# MCU.net
KiCad netlist of a schematic drawn in Altium Designer
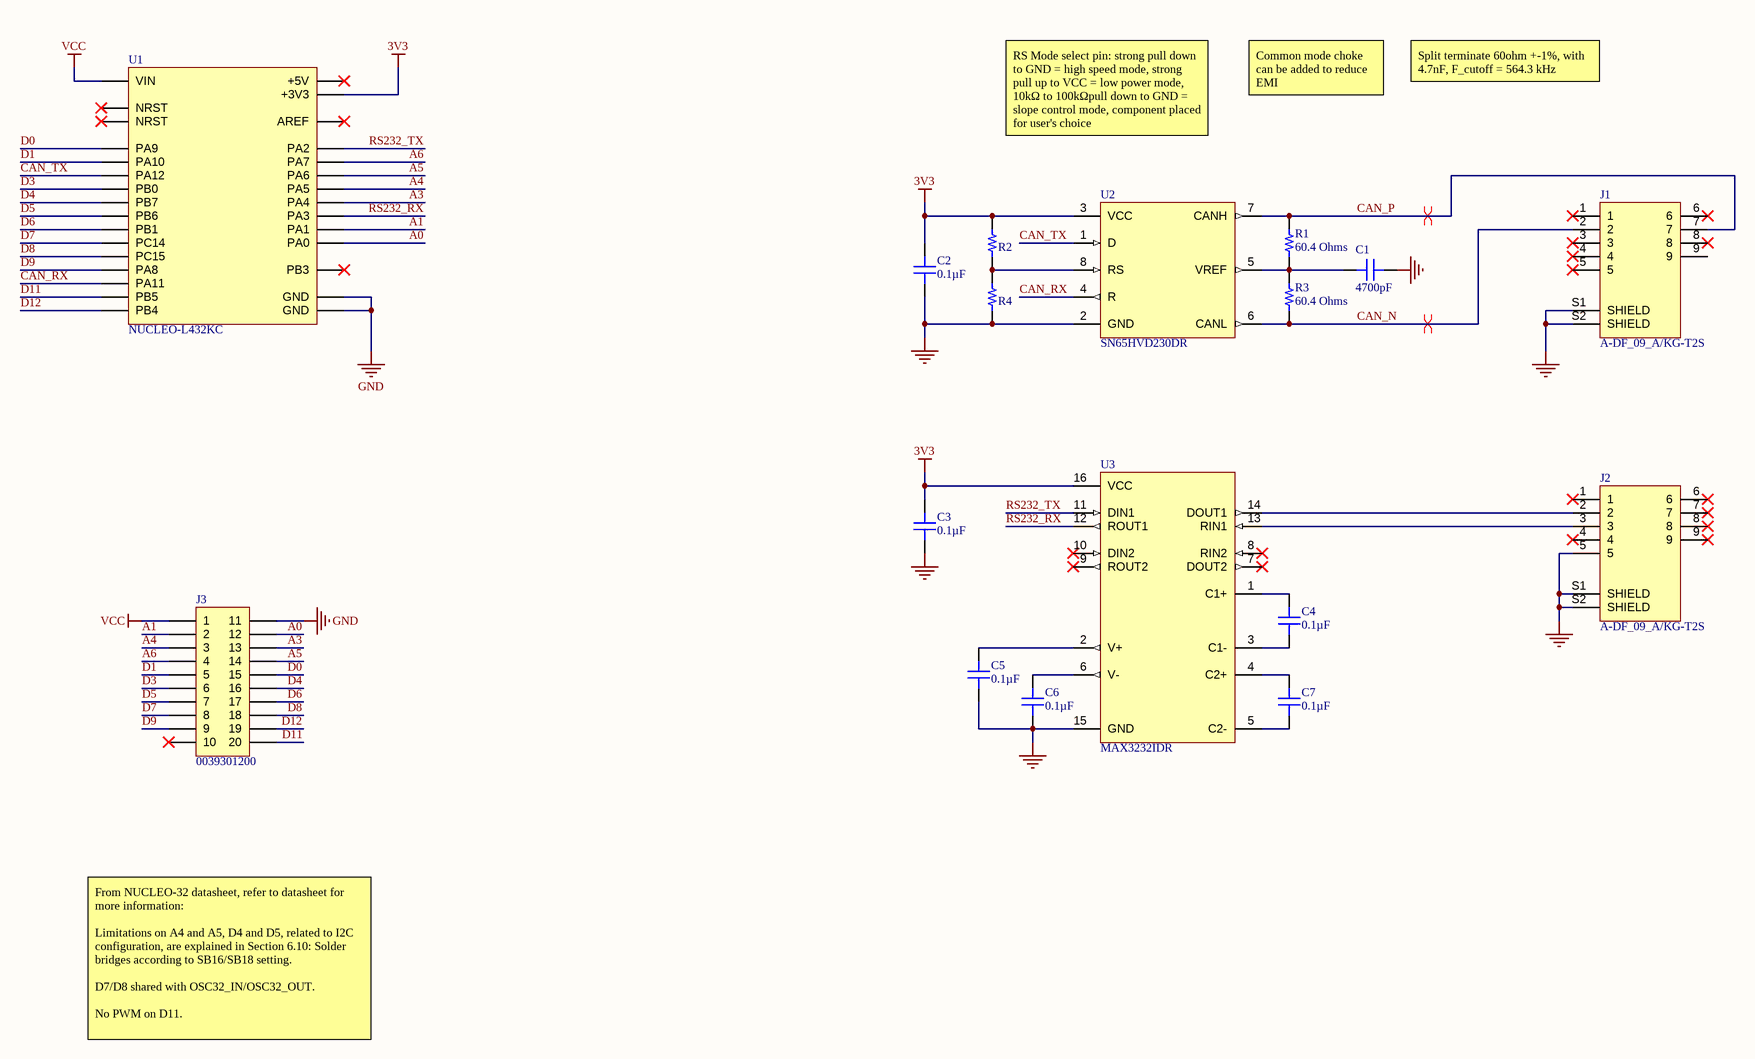
[diagram p0: MCU.SchDoc]

(export (version "E")
  (design (tool "Eeschema 10.0.6"))
  (components
    (comp (ref "C1")
      (value "4700pF")
      (footprint "CAP 0603_1608")
      (description "CAP CER 4700PF 50V X7R 0603")
      (fields
        (field (name "PART NUMBER") "CGA3E2X7R1H472K080AA")
        (field (name "MANUFACTURER") "TDK Corporation")
      )
      (libsource (lib "Celestial Altium Library - altium_library") (part "Capacitor"))
    )
    (comp (ref "C2")
      (value "0.1µF")
      (footprint "CAP 0603_1608")
      (description "CAP CER 0.1UF 25V X7R 0603")
      (fields
        (field (name "PART NUMBER") "CL10B104KA8NNNC")
        (field (name "MANUFACTURER") "Samsung Electro-Mechanics")
      )
      (libsource (lib "Celestial Altium Library - altium_library") (part "Capacitor"))
    )
    (comp (ref "C3")
      (value "0.1µF")
      (footprint "CAP 0603_1608")
      (description "CAP CER 0.1UF 25V X7R 0603")
      (fields
        (field (name "PART NUMBER") "CL10B104KA8NNNC")
        (field (name "MANUFACTURER") "Samsung Electro-Mechanics")
      )
      (libsource (lib "Celestial Altium Library - altium_library") (part "Capacitor"))
    )
    (comp (ref "C4")
      (value "0.1µF")
      (footprint "CAP 0603_1608")
      (description "CAP CER 0.1UF 25V X7R 0603")
      (fields
        (field (name "PART NUMBER") "CL10B104KA8NNNC")
        (field (name "MANUFACTURER") "Samsung Electro-Mechanics")
      )
      (libsource (lib "Celestial Altium Library - altium_library") (part "Capacitor"))
    )
    (comp (ref "C5")
      (value "0.1µF")
      (footprint "CAP 0603_1608")
      (description "CAP CER 0.1UF 25V X7R 0603")
      (fields
        (field (name "PART NUMBER") "CL10B104KA8NNNC")
        (field (name "MANUFACTURER") "Samsung Electro-Mechanics")
      )
      (libsource (lib "Celestial Altium Library - altium_library") (part "Capacitor"))
    )
    (comp (ref "C6")
      (value "0.1µF")
      (footprint "CAP 0603_1608")
      (description "CAP CER 0.1UF 25V X7R 0603")
      (fields
        (field (name "PART NUMBER") "CL10B104KA8NNNC")
        (field (name "MANUFACTURER") "Samsung Electro-Mechanics")
      )
      (libsource (lib "Celestial Altium Library - altium_library") (part "Capacitor"))
    )
    (comp (ref "C7")
      (value "0.1µF")
      (footprint "CAP 0603_1608")
      (description "CAP CER 0.1UF 25V X7R 0603")
      (fields
        (field (name "PART NUMBER") "CL10B104KA8NNNC")
        (field (name "MANUFACTURER") "Samsung Electro-Mechanics")
      )
      (libsource (lib "Celestial Altium Library - altium_library") (part "Capacitor"))
    )
    (comp (ref "J1")
      (value "A-DF_09_A/KG-T2S")
      (footprint "ASSMANN_A-DF09A/KG-T2S")
      (description "Conn D-Subminiature F 9 POS 2.77mm Solder RA Thru-Hole 9 Terminal 1 Port")
      (fields (field (name "MF") "{'manufacturer': u'Assmann WSW'}"))
      (libsource (lib "RTC_Mini_Symbols") (part "A-DF_09_A/KG-T2S"))
    )
    (comp (ref "J2")
      (value "A-DF_09_A/KG-T2S")
      (footprint "ASSMANN_A-DF09A/KG-T2S")
      (description "Conn D-Subminiature F 9 POS 2.77mm Solder RA Thru-Hole 9 Terminal 1 Port")
      (fields (field (name "MF") "{'manufacturer': u'Assmann WSW'}"))
      (libsource (lib "RTC_Mini_Symbols") (part "A-DF_09_A/KG-T2S"))
    )
    (comp (ref "J3")
      (value "0039301200")
      (footprint "MOLEX_0039301200")
      (description "Connector Header Through Hole, Right Angle 20 position 0.165\" (4.20mm)")
      (libsource (lib "RTC_Mini_Symbols") (part "0039301200"))
    )
    (comp (ref "R1")
      (value "60.4 Ohms")
      (footprint "RES 0603_1608")
      (description "RES 60.4 OHM 1% 1/10W 0603")
      (fields
        (field (name "PART NUMBER") "RMCF0603FT60R4")
        (field (name "MANUFACTURER") "Stackpole Electronics Inc")
      )
      (libsource (lib "Celestial Altium Library - altium_library") (part "Resistor"))
    )
    (comp (ref "R2")
      (value "~")
      (footprint "RES 0805_2012")
      (description "RES SMD 0 OHM JUMP 1/8W 0805")
      (fields (field (name "PART NUMBER") "CRCW08050000Z0EAC") (field (name "MANUFACTURER") "Vishay Dale"))
      (libsource (lib "Celestial Altium Library - altium_library") (part "Resistor"))
    )
    (comp (ref "R3")
      (value "60.4 Ohms")
      (footprint "RES 0603_1608")
      (description "RES 60.4 OHM 1% 1/10W 0603")
      (fields
        (field (name "PART NUMBER") "RMCF0603FT60R4")
        (field (name "MANUFACTURER") "Stackpole Electronics Inc")
      )
      (libsource (lib "Celestial Altium Library - altium_library") (part "Resistor"))
    )
    (comp (ref "R4")
      (value "~")
      (footprint "RES 0805_2012")
      (description "RES SMD 0 OHM JUMP 1/8W 0805")
      (fields (field (name "PART NUMBER") "CRCW08050000Z0EAC") (field (name "MANUFACTURER") "Vishay Dale"))
      (libsource (lib "Celestial Altium Library - altium_library") (part "Resistor"))
    )
    (comp (ref "U1")
      (value "NUCLEO-L432KC")
      (footprint "MODULE_NUCLEO-L432KC")
      (description "STM32 Nucleo-32 development board with STM32L432KC MCU, supports Arduino connectivity")
      (fields (field (name "MF") "{'manufacturer': u'STMicroelectronics'}"))
      (libsource (lib "RTC_Mini_Symbols") (part "NUCLEO-L432KC"))
    )
    (comp (ref "U2")
      (value "SN65HVD230DR")
      (footprint "SOIC127P599X175-8N")
      (description "3.3 V CAN Transceiver with Standby Mode 8-SOIC -40 to 85")
      (fields (field (name "MF") "{'manufacturer': u'Texas Instruments'}"))
      (libsource (lib "RTC_Mini_Symbols") (part "SN65HVD230DR"))
    )
    (comp (ref "U3")
      (value "MAX3232IDR")
      (footprint "SOIC127P600X175-16N")
      (description "3-V to 5.5-V multichannel RS-232 line driver & receiver 16-SOIC -40 to 85")
      (fields (field (name "MF") "{'manufacturer': u'Texas Instruments'}"))
      (libsource (lib "RTC_Mini_Symbols") (part "MAX3232IDR"))
    )
  )
  (nets
    (net (code "1") (name "/A0") (class "Default")
      (node (ref "J3") (pin "12") (pinfunction "12_12") (pintype "passive"))
      (node (ref "U1") (pin "CN4_12") (pinfunction "PA0_CN4_12") (pintype "passive"))
    )
    (net (code "2") (name "/A1") (class "Default")
      (node (ref "J3") (pin "2") (pinfunction "2_2") (pintype "passive"))
      (node (ref "U1") (pin "CN4_11") (pinfunction "PA1_CN4_11") (pintype "passive"))
    )
    (net (code "3") (name "/A3") (class "Default")
      (node (ref "J3") (pin "13") (pinfunction "13_13") (pintype "passive"))
      (node (ref "U1") (pin "CN4_9") (pinfunction "PA4_CN4_9") (pintype "passive"))
    )
    (net (code "4") (name "/A4") (class "Default")
      (node (ref "J3") (pin "3") (pinfunction "3_3") (pintype "passive"))
      (node (ref "U1") (pin "CN4_8") (pinfunction "PA5_CN4_8") (pintype "passive"))
    )
    (net (code "5") (name "/A5") (class "Default")
      (node (ref "J3") (pin "14") (pinfunction "14_14") (pintype "passive"))
      (node (ref "U1") (pin "CN4_7") (pinfunction "PA6_CN4_7") (pintype "passive"))
    )
    (net (code "6") (name "/A6") (class "Default")
      (node (ref "J3") (pin "4") (pinfunction "4_4") (pintype "passive"))
      (node (ref "U1") (pin "CN4_6") (pinfunction "PA7_CN4_6") (pintype "passive"))
    )
    (net (code "7") (name "/CAN_N") (class "Default")
      (node (ref "J1") (pin "2") (pinfunction "2_2") (pintype "passive"))
      (node (ref "R3") (pin "2") (pinfunction "2_2") (pintype "passive"))
      (node (ref "U2") (pin "6") (pinfunction "CANL_6") (pintype "output"))
    )
    (net (code "8") (name "/CAN_P") (class "Default")
      (node (ref "J1") (pin "7") (pinfunction "7_7") (pintype "passive"))
      (node (ref "R1") (pin "1") (pinfunction "1_1") (pintype "passive"))
      (node (ref "U2") (pin "7") (pinfunction "CANH_7") (pintype "output"))
    )
    (net (code "9") (name "/CAN_RX") (class "Default")
      (node (ref "U1") (pin "CN3_13") (pinfunction "PA11_CN3_13") (pintype "passive"))
      (node (ref "U2") (pin "4") (pinfunction "R_4") (pintype "output"))
    )
    (net (code "10") (name "/CAN_TX") (class "Default")
      (node (ref "U1") (pin "CN3_5") (pinfunction "PA12_CN3_5") (pintype "passive"))
      (node (ref "U2") (pin "1") (pinfunction "D_1") (pintype "input"))
    )
    (net (code "11") (name "/D0") (class "Default")
      (node (ref "J3") (pin "15") (pinfunction "15_15") (pintype "passive"))
      (node (ref "U1") (pin "CN3_1") (pinfunction "PA9_CN3_1") (pintype "passive"))
    )
    (net (code "12") (name "/D1") (class "Default")
      (node (ref "J3") (pin "5") (pinfunction "5_5") (pintype "passive"))
      (node (ref "U1") (pin "CN3_2") (pinfunction "PA10_CN3_2") (pintype "passive"))
    )
    (net (code "13") (name "/D3") (class "Default")
      (node (ref "J3") (pin "6") (pinfunction "6_6") (pintype "passive"))
      (node (ref "U1") (pin "CN3_6") (pinfunction "PB0_CN3_6") (pintype "passive"))
    )
    (net (code "14") (name "/D4") (class "Default")
      (node (ref "J3") (pin "16") (pinfunction "16_16") (pintype "passive"))
      (node (ref "U1") (pin "CN3_7") (pinfunction "PB7_CN3_7") (pintype "passive"))
    )
    (net (code "15") (name "/D5") (class "Default")
      (node (ref "J3") (pin "7") (pinfunction "7_7") (pintype "passive"))
      (node (ref "U1") (pin "CN3_8") (pinfunction "PB6_CN3_8") (pintype "passive"))
    )
    (net (code "16") (name "/D6") (class "Default")
      (node (ref "J3") (pin "17") (pinfunction "17_17") (pintype "passive"))
      (node (ref "U1") (pin "CN3_9") (pinfunction "PB1_CN3_9") (pintype "passive"))
    )
    (net (code "17") (name "/D7") (class "Default")
      (node (ref "J3") (pin "8") (pinfunction "8_8") (pintype "passive"))
      (node (ref "U1") (pin "CN3_10") (pinfunction "PC14_CN3_10") (pintype "passive"))
    )
    (net (code "18") (name "/D8") (class "Default")
      (node (ref "J3") (pin "18") (pinfunction "18_18") (pintype "passive"))
      (node (ref "U1") (pin "CN3_11") (pinfunction "PC15_CN3_11") (pintype "passive"))
    )
    (net (code "19") (name "/D9") (class "Default")
      (node (ref "J3") (pin "9") (pinfunction "9_9") (pintype "passive"))
      (node (ref "U1") (pin "CN3_12") (pinfunction "PA8_CN3_12") (pintype "passive"))
    )
    (net (code "20") (name "/D11") (class "Default")
      (node (ref "J3") (pin "20") (pinfunction "20_20") (pintype "passive"))
      (node (ref "U1") (pin "CN3_14") (pinfunction "PB5_CN3_14") (pintype "passive"))
    )
    (net (code "21") (name "/D12") (class "Default")
      (node (ref "J3") (pin "19") (pinfunction "19_19") (pintype "passive"))
      (node (ref "U1") (pin "CN3_15") (pinfunction "PB4_CN3_15") (pintype "passive"))
    )
    (net (code "22") (name "/RS232_RX") (class "Default")
      (node (ref "U1") (pin "CN4_10") (pinfunction "PA3_CN4_10") (pintype "passive"))
      (node (ref "U3") (pin "12") (pinfunction "ROUT1_12") (pintype "output"))
    )
    (net (code "23") (name "/RS232_TX") (class "Default")
      (node (ref "U1") (pin "CN4_5") (pinfunction "PA2_CN4_5") (pintype "passive"))
      (node (ref "U3") (pin "11") (pinfunction "DIN1_11") (pintype "input"))
    )
    (net (code "24") (name "3V3") (class "Default")
      (node (ref "C2") (pin "2") (pinfunction "2_2") (pintype "passive"))
      (node (ref "C3") (pin "2") (pinfunction "2_2") (pintype "passive"))
      (node (ref "R2") (pin "2") (pinfunction "2_2") (pintype "passive"))
      (node (ref "U1") (pin "CN4_14") (pinfunction "+3V3_CN4_14") (pintype "power_in"))
      (node (ref "U2") (pin "3") (pinfunction "VCC_3") (pintype "power_in"))
      (node (ref "U3") (pin "16") (pinfunction "VCC_16") (pintype "power_in"))
    )
    (net (code "25") (name "GND") (class "Default")
      (node (ref "C1") (pin "2") (pinfunction "2_2") (pintype "passive"))
      (node (ref "C2") (pin "1") (pinfunction "1_1") (pintype "passive"))
      (node (ref "C3") (pin "1") (pinfunction "1_1") (pintype "passive"))
      (node (ref "C5") (pin "1") (pinfunction "1_1") (pintype "passive"))
      (node (ref "C6") (pin "1") (pinfunction "1_1") (pintype "passive"))
      (node (ref "J1") (pin "S1") (pinfunction "SHIELD_S1") (pintype "passive"))
      (node (ref "J1") (pin "S2") (pinfunction "SHIELD_S2") (pintype "passive"))
      (node (ref "J2") (pin "5") (pinfunction "5_5") (pintype "passive"))
      (node (ref "J2") (pin "S1") (pinfunction "SHIELD_S1") (pintype "passive"))
      (node (ref "J2") (pin "S2") (pinfunction "SHIELD_S2") (pintype "passive"))
      (node (ref "J3") (pin "11") (pinfunction "11_11") (pintype "passive"))
      (node (ref "R4") (pin "1") (pinfunction "1_1") (pintype "passive"))
      (node (ref "U1") (pin "CN3_4") (pinfunction "GND_CN3_4") (pintype "power_in"))
      (node (ref "U1") (pin "CN4_2") (pinfunction "GND_CN4_2") (pintype "power_in"))
      (node (ref "U2") (pin "2") (pinfunction "GND_2") (pintype "power_in"))
      (node (ref "U3") (pin "15") (pinfunction "GND_15") (pintype "power_in"))
    )
    (net (code "26") (name "Net-(U2-RS)") (class "Default")
      (node (ref "R2") (pin "1") (pinfunction "1_1") (pintype "passive"))
      (node (ref "R4") (pin "2") (pinfunction "2_2") (pintype "passive"))
      (node (ref "U2") (pin "8") (pinfunction "RS_8") (pintype "input"))
    )
    (net (code "27") (name "Net-(U2-VREF)") (class "Default")
      (node (ref "C1") (pin "1") (pinfunction "1_1") (pintype "passive"))
      (node (ref "R1") (pin "2") (pinfunction "2_2") (pintype "passive"))
      (node (ref "R3") (pin "1") (pinfunction "1_1") (pintype "passive"))
      (node (ref "U2") (pin "5") (pinfunction "VREF_5") (pintype "output"))
    )
    (net (code "28") (name "Net-(U3-C1+)") (class "Default")
      (node (ref "C4") (pin "2") (pinfunction "2_2") (pintype "passive"))
      (node (ref "U3") (pin "1") (pinfunction "C1+_1") (pintype "passive"))
    )
    (net (code "29") (name "Net-(U3-C1-)") (class "Default")
      (node (ref "C4") (pin "1") (pinfunction "1_1") (pintype "passive"))
      (node (ref "U3") (pin "3") (pinfunction "C1-_3") (pintype "passive"))
    )
    (net (code "30") (name "Net-(U3-C2+)") (class "Default")
      (node (ref "C7") (pin "2") (pinfunction "2_2") (pintype "passive"))
      (node (ref "U3") (pin "4") (pinfunction "C2+_4") (pintype "passive"))
    )
    (net (code "31") (name "Net-(U3-C2-)") (class "Default")
      (node (ref "C7") (pin "1") (pinfunction "1_1") (pintype "passive"))
      (node (ref "U3") (pin "5") (pinfunction "C2-_5") (pintype "passive"))
    )
    (net (code "32") (name "Net-(U3-DOUT1)") (class "Default")
      (node (ref "J2") (pin "2") (pinfunction "2_2") (pintype "passive"))
      (node (ref "U3") (pin "14") (pinfunction "DOUT1_14") (pintype "output"))
    )
    (net (code "33") (name "Net-(U3-RIN1)") (class "Default")
      (node (ref "J2") (pin "3") (pinfunction "3_3") (pintype "passive"))
      (node (ref "U3") (pin "13") (pinfunction "RIN1_13") (pintype "input"))
    )
    (net (code "34") (name "Net-(U3-V+)") (class "Default")
      (node (ref "C5") (pin "2") (pinfunction "2_2") (pintype "passive"))
      (node (ref "U3") (pin "2") (pinfunction "V+_2") (pintype "output"))
    )
    (net (code "35") (name "Net-(U3-V-)") (class "Default")
      (node (ref "C6") (pin "2") (pinfunction "2_2") (pintype "passive"))
      (node (ref "U3") (pin "6") (pinfunction "V-_6") (pintype "output"))
    )
    (net (code "36") (name "VCC") (class "Default")
      (node (ref "J3") (pin "1") (pinfunction "1_1") (pintype "passive"))
      (node (ref "U1") (pin "CN4_1") (pinfunction "VIN_CN4_1") (pintype "power_in"))
    )
    (net (code "37") (name "unconnected-(J1-Pad1)") (class "Default")
      (node (ref "J1") (pin "1") (pinfunction "1_1") (pintype "passive+no_connect"))
    )
    (net (code "38") (name "unconnected-(J1-Pad3)") (class "Default")
      (node (ref "J1") (pin "3") (pinfunction "3_3") (pintype "passive+no_connect"))
    )
    (net (code "39") (name "unconnected-(J1-Pad4)") (class "Default")
      (node (ref "J1") (pin "4") (pinfunction "4_4") (pintype "passive+no_connect"))
    )
    (net (code "40") (name "unconnected-(J1-Pad5)") (class "Default")
      (node (ref "J1") (pin "5") (pinfunction "5_5") (pintype "passive+no_connect"))
    )
    (net (code "41") (name "unconnected-(J1-Pad6)") (class "Default")
      (node (ref "J1") (pin "6") (pinfunction "6_6") (pintype "passive+no_connect"))
    )
    (net (code "42") (name "unconnected-(J1-Pad8)") (class "Default")
      (node (ref "J1") (pin "8") (pinfunction "8_8") (pintype "passive+no_connect"))
    )
    (net (code "43") (name "unconnected-(J1-Pad9)") (class "Default")
      (node (ref "J1") (pin "9") (pinfunction "9_9") (pintype "passive"))
    )
    (net (code "44") (name "unconnected-(J2-Pad1)") (class "Default")
      (node (ref "J2") (pin "1") (pinfunction "1_1") (pintype "passive+no_connect"))
    )
    (net (code "45") (name "unconnected-(J2-Pad4)") (class "Default")
      (node (ref "J2") (pin "4") (pinfunction "4_4") (pintype "passive+no_connect"))
    )
    (net (code "46") (name "unconnected-(J2-Pad6)") (class "Default")
      (node (ref "J2") (pin "6") (pinfunction "6_6") (pintype "passive+no_connect"))
    )
    (net (code "47") (name "unconnected-(J2-Pad7)") (class "Default")
      (node (ref "J2") (pin "7") (pinfunction "7_7") (pintype "passive+no_connect"))
    )
    (net (code "48") (name "unconnected-(J2-Pad8)") (class "Default")
      (node (ref "J2") (pin "8") (pinfunction "8_8") (pintype "passive+no_connect"))
    )
    (net (code "49") (name "unconnected-(J2-Pad9)") (class "Default")
      (node (ref "J2") (pin "9") (pinfunction "9_9") (pintype "passive+no_connect"))
    )
    (net (code "50") (name "unconnected-(J3-Pad10)") (class "Default")
      (node (ref "J3") (pin "10") (pinfunction "10_10") (pintype "passive+no_connect"))
    )
    (net (code "51") (name "unconnected-(U1-+5V-PadCN4_4)") (class "Default")
      (node (ref "U1") (pin "CN4_4") (pinfunction "+5V_CN4_4") (pintype "power_in+no_connect"))
    )
    (net (code "52") (name "unconnected-(U1-AREF-PadCN4_13)") (class "Default")
      (node (ref "U1") (pin "CN4_13") (pinfunction "AREF_CN4_13") (pintype "passive+no_connect"))
    )
    (net (code "53") (name "unconnected-(U1-NRST-PadCN3_3)") (class "Default")
      (node (ref "U1") (pin "CN3_3") (pinfunction "NRST_CN3_3") (pintype "passive+no_connect"))
    )
    (net (code "54") (name "unconnected-(U1-NRST-PadCN4_3)") (class "Default")
      (node (ref "U1") (pin "CN4_3") (pinfunction "NRST_CN4_3") (pintype "passive+no_connect"))
    )
    (net (code "55") (name "unconnected-(U1-PB3-PadCN4_15)") (class "Default")
      (node (ref "U1") (pin "CN4_15") (pinfunction "PB3_CN4_15") (pintype "passive+no_connect"))
    )
    (net (code "56") (name "unconnected-(U3-DIN2-Pad10)") (class "Default")
      (node (ref "U3") (pin "10") (pinfunction "DIN2_10") (pintype "input+no_connect"))
    )
    (net (code "57") (name "unconnected-(U3-DOUT2-Pad7)") (class "Default")
      (node (ref "U3") (pin "7") (pinfunction "DOUT2_7") (pintype "output+no_connect"))
    )
    (net (code "58") (name "unconnected-(U3-RIN2-Pad8)") (class "Default")
      (node (ref "U3") (pin "8") (pinfunction "RIN2_8") (pintype "input+no_connect"))
    )
    (net (code "59") (name "unconnected-(U3-ROUT2-Pad9)") (class "Default")
      (node (ref "U3") (pin "9") (pinfunction "ROUT2_9") (pintype "output+no_connect"))
    )
  )
)
